# backplane.net
KiCad netlist of a schematic drawn in Altium Designer
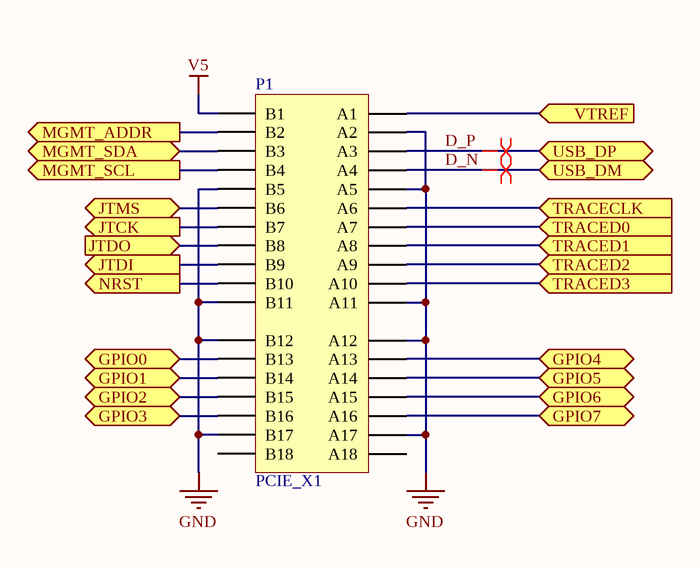
[diagram p0: backplane.SchDoc]

(export (version "E")
  (design (tool "Eeschema 10.0.6"))
  (components
    (comp (ref "P1") (value "PCIE_X1") (footprint "PCIE_X1_EDGE") (libsource (lib "misc") (part "PCIE_X1")))
  )
  (nets
    (net (code "1") (name "/D_N") (class "Default")
      (node (ref "P1") (pin "A4") (pinfunction "A4_A4") (pintype "passive"))
    )
    (net (code "2") (name "/D_P") (class "Default")
      (node (ref "P1") (pin "A3") (pinfunction "A3_A3") (pintype "passive"))
    )
    (net (code "3") (name "/GPIO0") (class "Default")
      (node (ref "P1") (pin "B13") (pinfunction "B13_B13") (pintype "passive"))
    )
    (net (code "4") (name "/GPIO1") (class "Default")
      (node (ref "P1") (pin "B14") (pinfunction "B14_B14") (pintype "passive"))
    )
    (net (code "5") (name "/GPIO2") (class "Default")
      (node (ref "P1") (pin "B15") (pinfunction "B15_B15") (pintype "passive"))
    )
    (net (code "6") (name "/GPIO3") (class "Default")
      (node (ref "P1") (pin "B16") (pinfunction "B16_B16") (pintype "passive"))
    )
    (net (code "7") (name "/GPIO4") (class "Default")
      (node (ref "P1") (pin "A13") (pinfunction "A13_A13") (pintype "passive"))
    )
    (net (code "8") (name "/GPIO5") (class "Default")
      (node (ref "P1") (pin "A14") (pinfunction "A14_A14") (pintype "passive"))
    )
    (net (code "9") (name "/GPIO6") (class "Default")
      (node (ref "P1") (pin "A15") (pinfunction "A15_A15") (pintype "passive"))
    )
    (net (code "10") (name "/GPIO7") (class "Default")
      (node (ref "P1") (pin "A16") (pinfunction "A16_A16") (pintype "passive"))
    )
    (net (code "11") (name "/JTCK") (class "Default")
      (node (ref "P1") (pin "B7") (pinfunction "B7_B7") (pintype "passive"))
    )
    (net (code "12") (name "/JTDI") (class "Default")
      (node (ref "P1") (pin "B9") (pinfunction "B9_B9") (pintype "passive"))
    )
    (net (code "13") (name "/JTDO") (class "Default")
      (node (ref "P1") (pin "B8") (pinfunction "B8_B8") (pintype "passive"))
    )
    (net (code "14") (name "/JTMS") (class "Default")
      (node (ref "P1") (pin "B6") (pinfunction "B6_B6") (pintype "passive"))
    )
    (net (code "15") (name "/MGMT_ADDR") (class "Default")
      (node (ref "P1") (pin "B2") (pinfunction "B2_B2") (pintype "passive"))
    )
    (net (code "16") (name "/MGMT_SCL") (class "Default")
      (node (ref "P1") (pin "B4") (pinfunction "B4_B4") (pintype "passive"))
    )
    (net (code "17") (name "/MGMT_SDA") (class "Default")
      (node (ref "P1") (pin "B3") (pinfunction "B3_B3") (pintype "passive"))
    )
    (net (code "18") (name "/NRST") (class "Default")
      (node (ref "P1") (pin "B10") (pinfunction "B10_B10") (pintype "passive"))
    )
    (net (code "19") (name "/TRACECLK") (class "Default")
      (node (ref "P1") (pin "A6") (pinfunction "A6_A6") (pintype "passive"))
    )
    (net (code "20") (name "/TRACED0") (class "Default")
      (node (ref "P1") (pin "A7") (pinfunction "A7_A7") (pintype "passive"))
    )
    (net (code "21") (name "/TRACED1") (class "Default")
      (node (ref "P1") (pin "A8") (pinfunction "A8_A8") (pintype "passive"))
    )
    (net (code "22") (name "/TRACED2") (class "Default")
      (node (ref "P1") (pin "A9") (pinfunction "A9_A9") (pintype "passive"))
    )
    (net (code "23") (name "/TRACED3") (class "Default")
      (node (ref "P1") (pin "A10") (pinfunction "A10_A10") (pintype "passive"))
    )
    (net (code "24") (name "/VTREF") (class "Default")
      (node (ref "P1") (pin "A1") (pinfunction "A1_A1") (pintype "passive"))
    )
    (net (code "25") (name "GND") (class "Default")
      (node (ref "P1") (pin "A11") (pinfunction "A11_A11") (pintype "passive"))
      (node (ref "P1") (pin "A12") (pinfunction "A12_A12") (pintype "passive"))
      (node (ref "P1") (pin "A17") (pinfunction "A17_A17") (pintype "passive"))
      (node (ref "P1") (pin "A2") (pinfunction "A2_A2") (pintype "passive"))
      (node (ref "P1") (pin "A5") (pinfunction "A5_A5") (pintype "passive"))
      (node (ref "P1") (pin "B11") (pinfunction "B11_B11") (pintype "passive"))
      (node (ref "P1") (pin "B12") (pinfunction "B12_B12") (pintype "passive"))
      (node (ref "P1") (pin "B17") (pinfunction "B17_B17") (pintype "passive"))
      (node (ref "P1") (pin "B5") (pinfunction "B5_B5") (pintype "passive"))
    )
    (net (code "26") (name "V5") (class "Default")
      (node (ref "P1") (pin "B1") (pinfunction "B1_B1") (pintype "passive"))
    )
    (net (code "27") (name "unconnected-(P1-PadA18)") (class "Default")
      (node (ref "P1") (pin "A18") (pinfunction "A18_A18") (pintype "passive"))
    )
    (net (code "28") (name "unconnected-(P1-PadB18)") (class "Default")
      (node (ref "P1") (pin "B18") (pinfunction "B18_B18") (pintype "passive"))
    )
  )
)
